# Power.net
KiCad netlist of a schematic drawn in Altium Designer
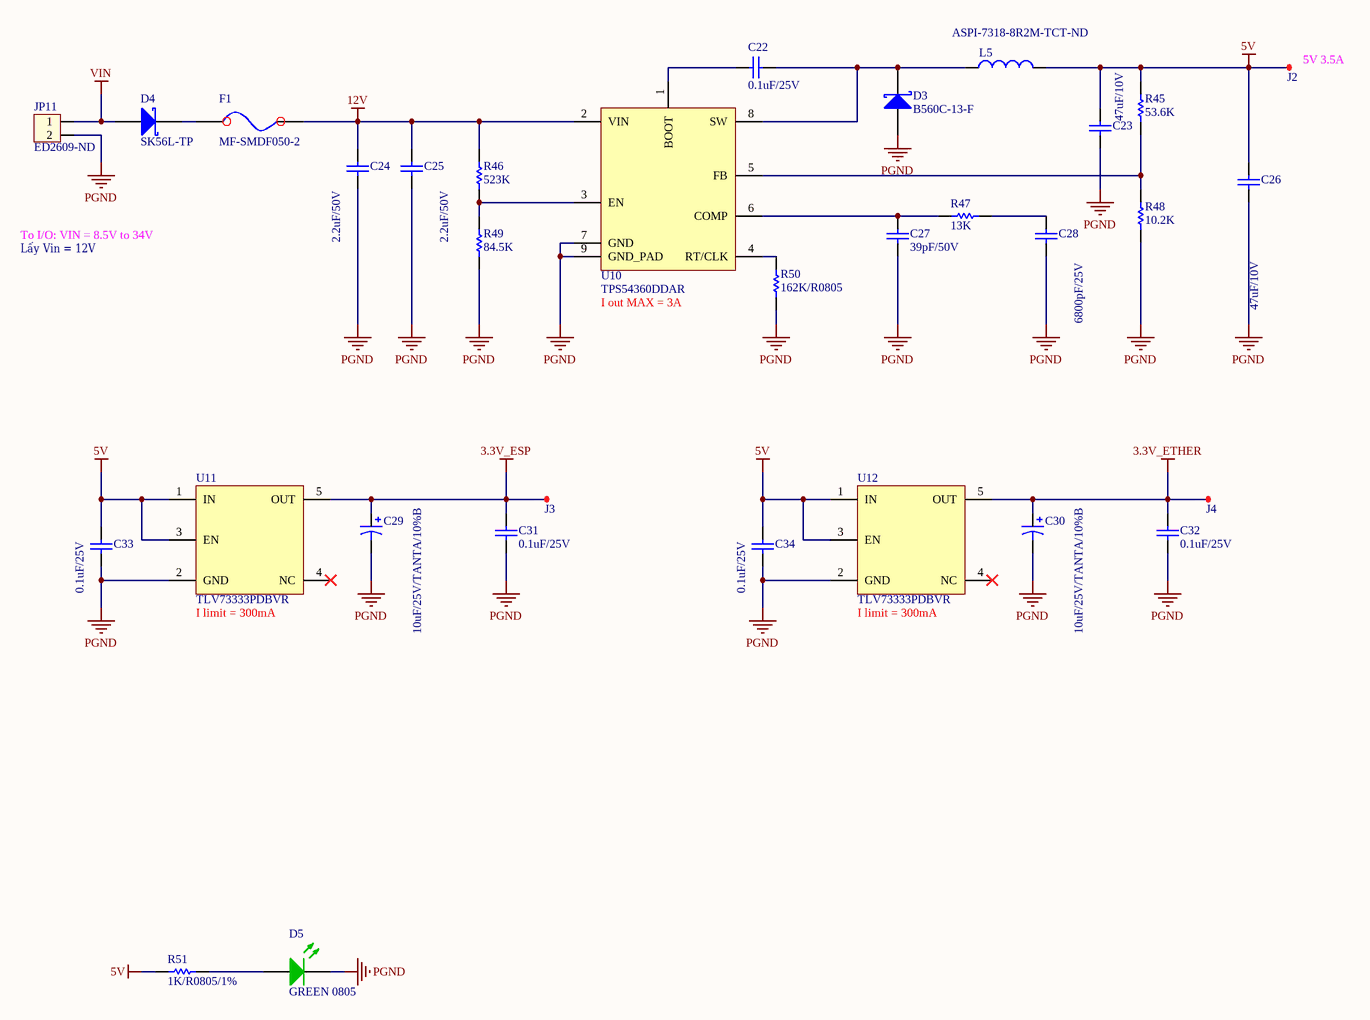
[diagram p0: Power.SchDoc]

(export (version "E")
  (design (tool "Eeschema 10.0.6"))
  (components
    (comp (ref "C22")
      (value "0.1uF/25V")
      (footprint "CAP_CERA_C2012(CC0805INCH)")
      (description "0.1µF ±10% 25V Ceramic Capacitor X7R 0805 (2012 Metric)")
      (fields (field (name "MANUFACTURER") "AVX Corporation"))
      (libsource (lib "GSHT_181013") (part "0.1uF/50V/C0603/10%"))
    )
    (comp (ref "C23")
      (value "47uF/10V")
      (footprint "CAP_CERA_C2012(CC0805INCH)")
      (description "47µF ±20% 10V Ceramic Capacitor X5R 0805 (2012 Metric)")
      (fields (field (name "MANUFACTURER") "Murata"))
      (libsource (lib "GSHT_181013") (part "0.1uF/50V/C0603/10%"))
    )
    (comp (ref "C24")
      (value "2.2uF/50V")
      (footprint "CAP_CERA_C2012(CC0805INCH)")
      (description "2.2µF ±10% 50V Ceramic Capacitor JB 0805 (2012 Metric)")
      (fields (field (name "MANUFACTURER") "TDK"))
      (libsource (lib "GSHT_181013") (part "1uF/50V/C0603/10%"))
    )
    (comp (ref "C25")
      (value "2.2uF/50V")
      (footprint "CAP_CERA_C2012(CC0805INCH)")
      (description "2.2µF ±10% 50V Ceramic Capacitor JB 0805 (2012 Metric)")
      (fields (field (name "MANUFACTURER") "TDK"))
      (libsource (lib "GSHT_181013") (part "1uF/50V/C0603/10%"))
    )
    (comp (ref "C26")
      (value "47uF/10V")
      (footprint "CAP_CERA_C2012(CC0805INCH)")
      (description "47µF ±20% 10V Ceramic Capacitor X5R 0805 (2012 Metric)")
      (fields (field (name "MANUFACTURER") "Murata"))
      (libsource (lib "GSHT_181013") (part "0.1uF/50V/C0603/10%"))
    )
    (comp (ref "C27")
      (value "39pF/50V")
      (footprint "CAP_CERA_C2012(CC0805INCH)")
      (description "39pF ±10% 50V Ceramic Capacitor C0G, NP0 0805 (2012 Metric)")
      (fields (field (name "MANUFACTURER") "KEMET"))
      (libsource (lib "GSHT_181013") (part "56pF/50V/C0603/5%"))
    )
    (comp (ref "C28")
      (value "6800pF/25V")
      (footprint "CAP_CERA_C2012(CC0805INCH)")
      (description "6800pF ±10% 25V Ceramic Capacitor X7R 0805 (2012 Metric)")
      (fields (field (name "MANUFACTURER") "Wurth Electronics Inc."))
      (libsource (lib "GSHT_181013") (part "10nF/50V/C0603/10%"))
    )
    (comp (ref "C29")
      (value "10uF/25V/TANTA/10%B")
      (footprint "CAP TANT CASE B SMD")
      (description "10µF Molded Tantalum Capacitors 25V 1411 (3528 Metric) 3 Ohm")
      (fields (field (name "MANUFACTURER") "KEMET"))
      (libsource (lib "GSHT_181013") (part "TAJB106M025RNJ"))
    )
    (comp (ref "C30")
      (value "10uF/25V/TANTA/10%B")
      (footprint "CAP TANT CASE B SMD")
      (description "10µF Molded Tantalum Capacitors 25V 1411 (3528 Metric) 3 Ohm")
      (fields (field (name "MANUFACTURER") "KEMET"))
      (libsource (lib "GSHT_181013") (part "TAJB106M025RNJ"))
    )
    (comp (ref "C31")
      (value "0.1uF/25V")
      (footprint "CAP_CERA_C2012(CC0805INCH)")
      (description "0.1µF ±10% 25V Ceramic Capacitor X7R 0805 (2012 Metric)")
      (fields (field (name "MANUFACTURER") "AVX Corporation"))
      (libsource (lib "GSHT_181013") (part "0.1uF/50V/C0603/10%"))
    )
    (comp (ref "C32")
      (value "0.1uF/25V")
      (footprint "CAP_CERA_C2012(CC0805INCH)")
      (description "0.1µF ±10% 25V Ceramic Capacitor X7R 0805 (2012 Metric)")
      (fields (field (name "MANUFACTURER") "AVX Corporation"))
      (libsource (lib "GSHT_181013") (part "0.1uF/50V/C0603/10%"))
    )
    (comp (ref "C33")
      (value "0.1uF/25V")
      (footprint "CAP_CERA_C2012(CC0805INCH)")
      (description "0.1µF ±10% 25V Ceramic Capacitor X7R 0805 (2012 Metric)")
      (fields (field (name "MANUFACTURER") "AVX Corporation"))
      (libsource (lib "GSHT_181013") (part "0.1uF/50V/C0603/10%"))
    )
    (comp (ref "C34")
      (value "0.1uF/25V")
      (footprint "CAP_CERA_C2012(CC0805INCH)")
      (description "0.1µF ±10% 25V Ceramic Capacitor X7R 0805 (2012 Metric)")
      (fields (field (name "MANUFACTURER") "AVX Corporation"))
      (libsource (lib "GSHT_181013") (part "0.1uF/50V/C0603/10%"))
    )
    (comp (ref "D3")
      (value "B560C-13-F")
      (footprint "2# B560C")
      (description "DIODE SCHOTTKY 60V 5A SMC")
      (libsource (lib "GSHT_181013") (part "2#B560C-13-F"))
    )
    (comp (ref "D4")
      (value "SK56L-TP")
      (footprint "30# SK56L-TPMSCT-ND")
      (description "DIODE SCHOTTKY 60V 5A DO214AB")
      (libsource (lib "GSHT_181013") (part "30# SK56L-TP"))
    )
    (comp (ref "D5")
      (value "GREEN 0805")
      (footprint "Led 0805G")
      (description "Green 571nm LED Indication - Discrete 2V 0805 (2012 Metric)")
      (libsource (lib "GSHT_181013") (part "LED GREEN 0603"))
    )
    (comp (ref "F1")
      (value "MF-SMDF050-2")
      (footprint "13# MF-SMDF050")
      (description "PTC RESET FUSE 60V 550MA 2018")
      (libsource (lib "GSHT_181013") (part "13#MF-SMDF050-2"))
    )
    (comp (ref "J2")
      (value "TEST POINT")
      (footprint "TEST POINT 1mm")
      (description "TPoint")
      (libsource (lib "GSHT_181013") (part "PAD 1mm"))
    )
    (comp (ref "J3")
      (value "TEST POINT")
      (footprint "TEST POINT 1mm")
      (description "TPoint")
      (libsource (lib "GSHT_181013") (part "PAD 1mm"))
    )
    (comp (ref "J4")
      (value "TEST POINT")
      (footprint "TEST POINT 1mm")
      (description "TPoint")
      (libsource (lib "GSHT_181013") (part "PAD 1mm"))
    )
    (comp (ref "JP11")
      (value "ED2609-ND")
      (footprint "DOMINO_OSTTC_2P")
      (description "2 Position Wire to Board Terminal Block Horizontal with Board 0.200\" (5.08mm) Through Hole")
      (libsource (lib "lpson") (part "Con2"))
    )
    (comp (ref "L5")
      (value "ASPI-7318-8R2M-TCT-ND")
      (footprint "ASPI-7318-8R2M-TCT-ND")
      (description "8.2µH Shielded Wirewound Inductor 4A 68 mOhm Max Nonstandard")
      (libsource (lib "lpson") (part "Inductor"))
    )
    (comp (ref "R45")
      (value "53.6K")
      (footprint "Res 0805 SMD")
      (description "53.6 kOhms ±1% 0.125W, 1/8W Chip Resistor 0805 (2012 Metric) Automotive AEC-Q200 Thick Film")
      (libsource (lib "GSHT_181013") (part "15K/R0603/1%"))
    )
    (comp (ref "R46")
      (value "523K")
      (footprint "Res 0805 SMD")
      (description "523 kOhms ±1% 0.125W, 1/8W Chip Resistor 0805 (2012 Metric) Automotive AEC-Q200 Thick Film")
      (libsource (lib "GSHT_181013") (part "249K/R0805/1%"))
    )
    (comp (ref "R47")
      (value "13K")
      (footprint "Res 0805 SMD")
      (description "13 kOhms ±1% 0.125W, 1/8W Chip Resistor 0805 (2012 Metric) Automotive AEC-Q200 Thick Film")
      (libsource (lib "GSHT_181013") (part "15K/R0603/1%"))
    )
    (comp (ref "R48")
      (value "10.2K")
      (footprint "Res 0805 SMD")
      (description "10.2 kOhms ±1% 0.125W, 1/8W Chip Resistor 0805 (2012 Metric) Automotive AEC-Q200 Thick Film")
      (libsource (lib "GSHT_181013") (part "3.3K/R0603/1%"))
    )
    (comp (ref "R49")
      (value "84.5K")
      (footprint "Res 0805 SMD")
      (description "84.5 kOhms ±1% 0.125W, 1/8W Chip Resistor 0805 (2012 Metric) Automotive AEC-Q200 Thick Film")
      (libsource (lib "GSHT_181013") (part "34.8K/R0805/1%"))
    )
    (comp (ref "R50")
      (value "162K/R0805")
      (footprint "Res 0805 SMD")
      (description "162 kOhms ±1% 0.125W, 1/8W Chip Resistor 0805 (2012 Metric) Automotive AEC-Q200 Thick Film")
      (libsource (lib "GSHT_181013") (part "200K/R0603/1%"))
    )
    (comp (ref "R51")
      (value "1K/R0805/1%")
      (footprint "Res 0805 SMD")
      (description "1 kOhms ±1% 0.125W, 1/8W Chip Resistor 0805 (2012 Metric) Automotive AEC-Q200 Thick Film")
      (libsource (lib "GSHT_181013") (part "200K/R0603/1%"))
    )
    (comp (ref "U10")
      (value "TPS54360DDAR")
      (footprint "21# TPS54360")
      (libsource (lib "GSHT_181013") (part "21#TPS54360DDAR"))
    )
    (comp (ref "U11")
      (value "TLV73333PDBVR")
      (footprint "20# TLV73333PDBVR - SOT23-65")
      (description "Linear Voltage Regulator IC Positive Fixed 1 Output 3.3V 300mA SOT-23-5")
      (libsource (lib "GSHT_181013") (part "20#TLV73333PDBVR"))
    )
    (comp (ref "U12")
      (value "TLV73333PDBVR")
      (footprint "20# TLV73333PDBVR - SOT23-65")
      (description "Linear Voltage Regulator IC Positive Fixed 1 Output 3.3V 300mA SOT-23-5")
      (libsource (lib "GSHT_181013") (part "20#TLV73333PDBVR"))
    )
  )
  (nets
    (net (code "1") (name "3.3V_ESP") (class "Default")
      (node (ref "C29") (pin "1") (pinfunction "1_1") (pintype "passive"))
      (node (ref "C31") (pin "2") (pinfunction "2_2") (pintype "passive"))
      (node (ref "J3") (pin "1") (pinfunction "TP_1") (pintype "passive"))
      (node (ref "U11") (pin "5") (pinfunction "OUT_5") (pintype "passive"))
    )
    (net (code "2") (name "3.3V_ETHER") (class "Default")
      (node (ref "C30") (pin "1") (pinfunction "1_1") (pintype "passive"))
      (node (ref "C32") (pin "2") (pinfunction "2_2") (pintype "passive"))
      (node (ref "J4") (pin "1") (pinfunction "TP_1") (pintype "passive"))
      (node (ref "U12") (pin "5") (pinfunction "OUT_5") (pintype "passive"))
    )
    (net (code "3") (name "5V") (class "Default")
      (node (ref "C23") (pin "2") (pinfunction "2_2") (pintype "passive"))
      (node (ref "C26") (pin "2") (pinfunction "2_2") (pintype "passive"))
      (node (ref "C33") (pin "2") (pinfunction "2_2") (pintype "passive"))
      (node (ref "C34") (pin "2") (pinfunction "2_2") (pintype "passive"))
      (node (ref "J2") (pin "1") (pinfunction "TP_1") (pintype "passive"))
      (node (ref "L5") (pin "2") (pinfunction "2_2") (pintype "passive"))
      (node (ref "R45") (pin "2") (pinfunction "2_2") (pintype "passive"))
      (node (ref "R51") (pin "1") (pinfunction "1_1") (pintype "passive"))
      (node (ref "U11") (pin "1") (pinfunction "IN_1") (pintype "passive"))
      (node (ref "U11") (pin "3") (pinfunction "EN_3") (pintype "passive"))
      (node (ref "U12") (pin "1") (pinfunction "IN_1") (pintype "passive"))
      (node (ref "U12") (pin "3") (pinfunction "EN_3") (pintype "passive"))
    )
    (net (code "4") (name "12V") (class "Default")
      (node (ref "C24") (pin "2") (pinfunction "2_2") (pintype "passive"))
      (node (ref "C25") (pin "2") (pinfunction "2_2") (pintype "passive"))
      (node (ref "F1") (pin "2") (pinfunction "OUT_2") (pintype "passive"))
      (node (ref "R46") (pin "2") (pinfunction "2_2") (pintype "passive"))
      (node (ref "U10") (pin "2") (pinfunction "VIN_2") (pintype "passive"))
    )
    (net (code "5") (name "Net-(C28-Pad2)") (class "Default")
      (node (ref "C28") (pin "2") (pinfunction "2_2") (pintype "passive"))
      (node (ref "R47") (pin "1") (pinfunction "1_1") (pintype "passive"))
    )
    (net (code "6") (name "Net-(D3-K)") (class "Default")
      (node (ref "C22") (pin "1") (pinfunction "1_1") (pintype "passive"))
      (node (ref "D3") (pin "2") (pinfunction "K_2") (pintype "passive"))
      (node (ref "L5") (pin "1") (pinfunction "1_1") (pintype "passive"))
      (node (ref "U10") (pin "8") (pinfunction "SW_8") (pintype "passive"))
    )
    (net (code "7") (name "Net-(D4-K)") (class "Default")
      (node (ref "D4") (pin "2") (pinfunction "K_2") (pintype "passive"))
      (node (ref "F1") (pin "1") (pinfunction "IN_1") (pintype "passive"))
    )
    (net (code "8") (name "Net-(D5-A)") (class "Default")
      (node (ref "D5") (pin "1") (pinfunction "A_1") (pintype "passive"))
      (node (ref "R51") (pin "2") (pinfunction "2_2") (pintype "passive"))
    )
    (net (code "9") (name "Net-(U10-BOOT)") (class "Default")
      (node (ref "C22") (pin "2") (pinfunction "2_2") (pintype "passive"))
      (node (ref "U10") (pin "1") (pinfunction "BOOT_1") (pintype "passive"))
    )
    (net (code "10") (name "Net-(U10-COMP)") (class "Default")
      (node (ref "C27") (pin "2") (pinfunction "2_2") (pintype "passive"))
      (node (ref "R47") (pin "2") (pinfunction "2_2") (pintype "passive"))
      (node (ref "U10") (pin "6") (pinfunction "COMP_6") (pintype "passive"))
    )
    (net (code "11") (name "Net-(U10-EN)") (class "Default")
      (node (ref "R46") (pin "1") (pinfunction "1_1") (pintype "passive"))
      (node (ref "R49") (pin "2") (pinfunction "2_2") (pintype "passive"))
      (node (ref "U10") (pin "3") (pinfunction "EN_3") (pintype "passive"))
    )
    (net (code "12") (name "Net-(U10-FB)") (class "Default")
      (node (ref "R45") (pin "1") (pinfunction "1_1") (pintype "passive"))
      (node (ref "R48") (pin "2") (pinfunction "2_2") (pintype "passive"))
      (node (ref "U10") (pin "5") (pinfunction "FB_5") (pintype "passive"))
    )
    (net (code "13") (name "Net-(U10-RT{slash}CLK)") (class "Default")
      (node (ref "R50") (pin "1") (pinfunction "1_1") (pintype "passive"))
      (node (ref "U10") (pin "4") (pinfunction "RT/CLK_4") (pintype "passive"))
    )
    (net (code "14") (name "PGND") (class "Default")
      (node (ref "C23") (pin "1") (pinfunction "1_1") (pintype "passive"))
      (node (ref "C24") (pin "1") (pinfunction "1_1") (pintype "passive"))
      (node (ref "C25") (pin "1") (pinfunction "1_1") (pintype "passive"))
      (node (ref "C26") (pin "1") (pinfunction "1_1") (pintype "passive"))
      (node (ref "C27") (pin "1") (pinfunction "1_1") (pintype "passive"))
      (node (ref "C28") (pin "1") (pinfunction "1_1") (pintype "passive"))
      (node (ref "C29") (pin "2") (pinfunction "2_2") (pintype "passive"))
      (node (ref "C30") (pin "2") (pinfunction "2_2") (pintype "passive"))
      (node (ref "C31") (pin "1") (pinfunction "1_1") (pintype "passive"))
      (node (ref "C32") (pin "1") (pinfunction "1_1") (pintype "passive"))
      (node (ref "C33") (pin "1") (pinfunction "1_1") (pintype "passive"))
      (node (ref "C34") (pin "1") (pinfunction "1_1") (pintype "passive"))
      (node (ref "D3") (pin "1") (pinfunction "A_1") (pintype "passive"))
      (node (ref "D5") (pin "2") (pinfunction "K_2") (pintype "passive"))
      (node (ref "JP11") (pin "2") (pinfunction "2_2") (pintype "passive"))
      (node (ref "R48") (pin "1") (pinfunction "1_1") (pintype "passive"))
      (node (ref "R49") (pin "1") (pinfunction "1_1") (pintype "passive"))
      (node (ref "R50") (pin "2") (pinfunction "2_2") (pintype "passive"))
      (node (ref "U10") (pin "7") (pinfunction "GND_7") (pintype "passive"))
      (node (ref "U10") (pin "9") (pinfunction "GND_PAD_9") (pintype "passive"))
      (node (ref "U11") (pin "2") (pinfunction "GND_2") (pintype "passive"))
      (node (ref "U12") (pin "2") (pinfunction "GND_2") (pintype "passive"))
    )
    (net (code "15") (name "VIN") (class "Default")
      (node (ref "D4") (pin "1") (pinfunction "A_1") (pintype "passive"))
      (node (ref "JP11") (pin "1") (pinfunction "1_1") (pintype "passive"))
    )
    (net (code "16") (name "unconnected-(U11-NC-Pad4)") (class "Default")
      (node (ref "U11") (pin "4") (pinfunction "NC_4") (pintype "passive+no_connect"))
    )
    (net (code "17") (name "unconnected-(U12-NC-Pad4)") (class "Default")
      (node (ref "U12") (pin "4") (pinfunction "NC_4") (pintype "passive+no_connect"))
    )
  )
)
